# ControlBoard.net
KiCad netlist of a schematic drawn in EAGLE
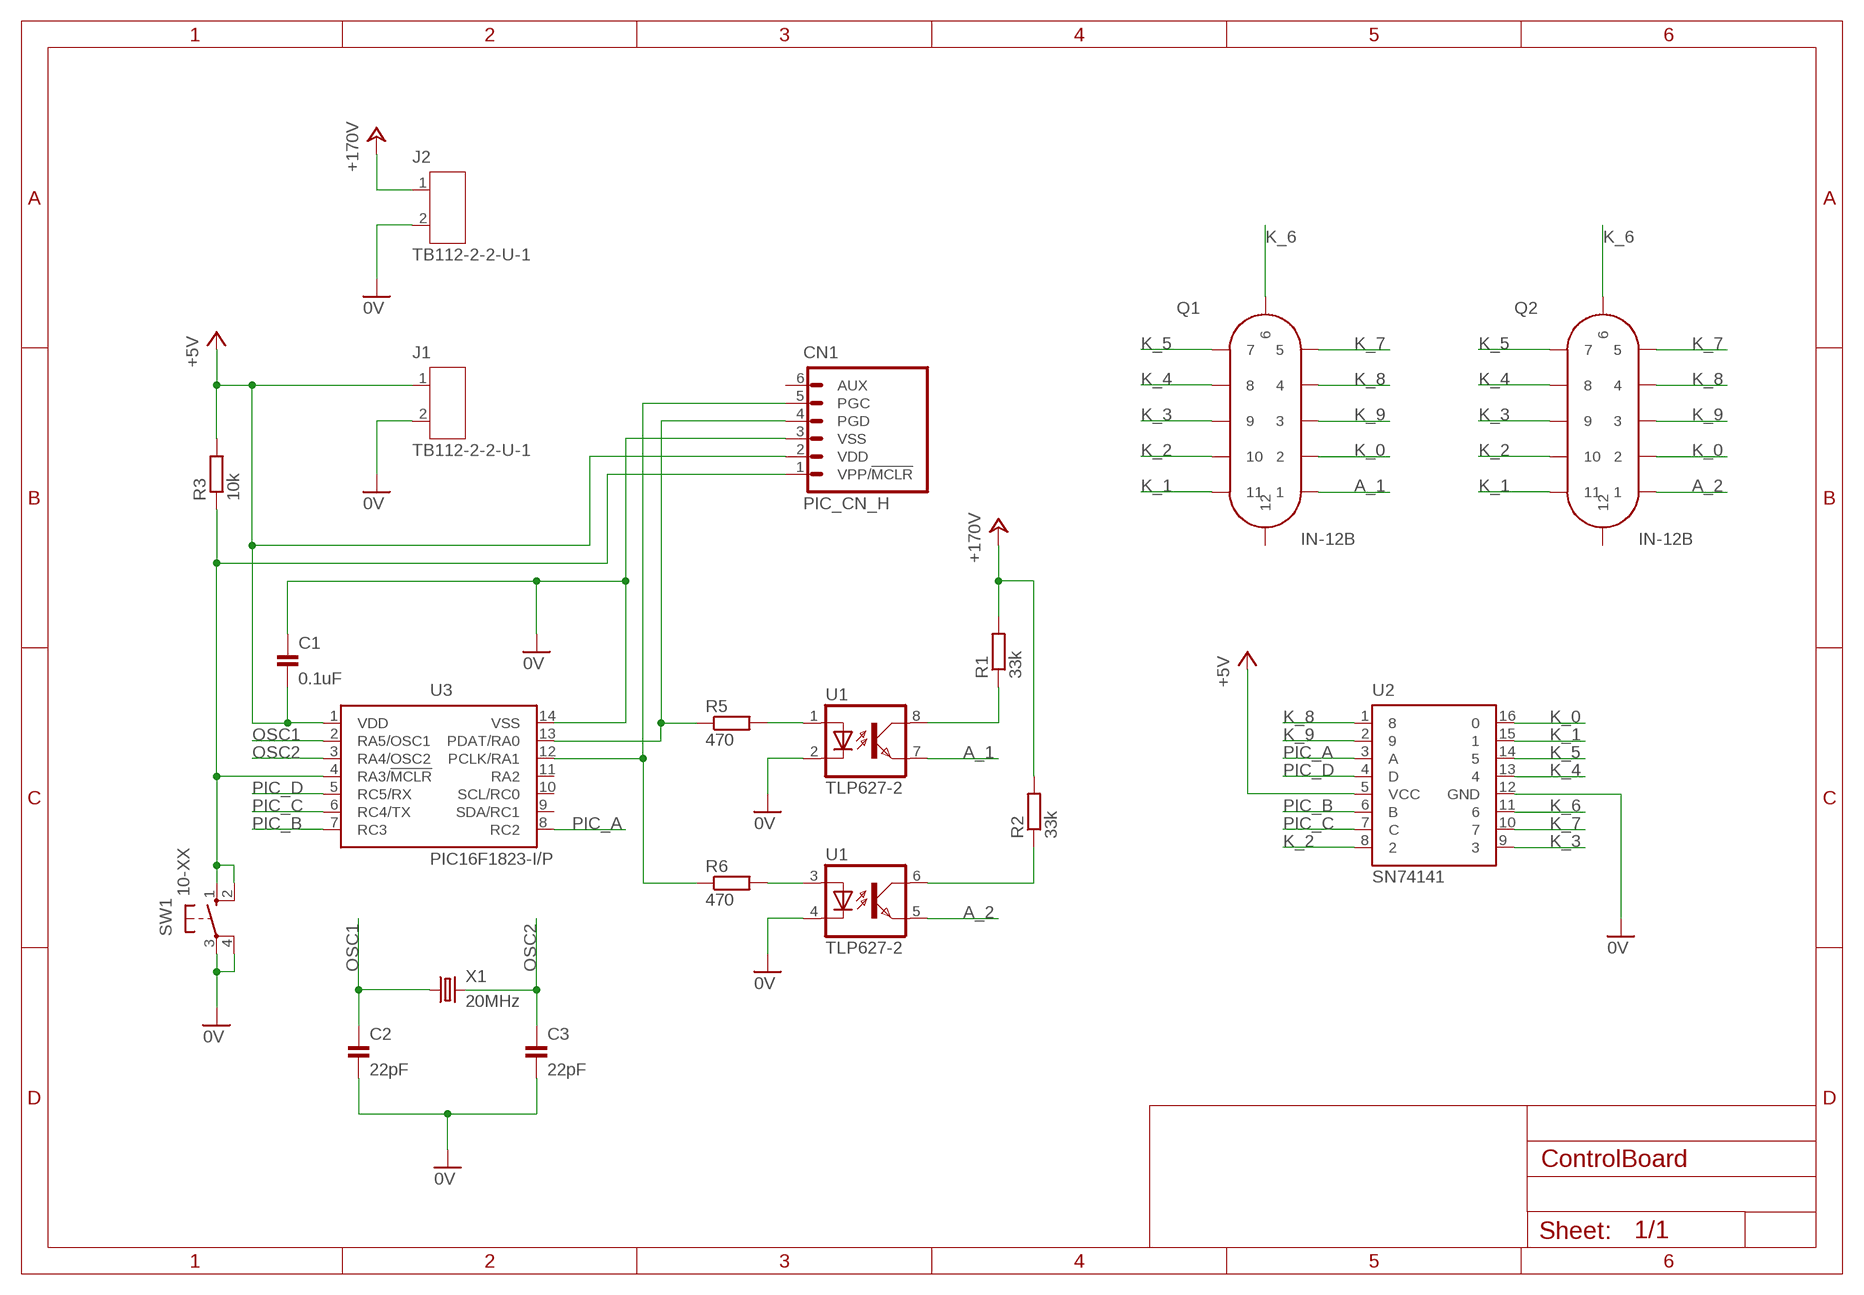
[diagram p0: schematic, sheet 1]

(export (version "E")
  (design (tool "Eeschema 10.0.6"))
  (components
    (comp (ref "C1")
      (value "0.1uF")
      (footprint "eagle-import:CAP_200MIL")
      (libsource (lib "eagle-import") (part "CAP_200MIL"))
    )
    (comp (ref "C2")
      (value "22pF")
      (footprint "eagle-import:CAP_100MIL")
      (libsource (lib "eagle-import") (part "CAP_100MIL"))
    )
    (comp (ref "C3")
      (value "22pF")
      (footprint "eagle-import:CAP_100MIL")
      (libsource (lib "eagle-import") (part "CAP_100MIL"))
    )
    (comp (ref "CN1")
      (value "PIC_CN_H")
      (footprint "eagle-import:HEADER_6PIN")
      (libsource (lib "eagle-import") (part "PIC_CN_H"))
    )
    (comp (ref "J1")
      (value "TB112-2-2-U-1")
      (footprint "eagle-import:TERMINAL_BLOCK_2PIN_200MIL")
      (libsource (lib "eagle-import") (part "TB112-2-2-U-1"))
    )
    (comp (ref "J2")
      (value "TB112-2-2-U-1")
      (footprint "eagle-import:TERMINAL_BLOCK_2PIN_200MIL")
      (libsource (lib "eagle-import") (part "TB112-2-2-U-1"))
    )
    (comp (ref "Q1")
      (value "IN-12B")
      (footprint "eagle-import:IN-12")
      (libsource (lib "eagle-import") (part "IN-12B"))
    )
    (comp (ref "Q2")
      (value "IN-12B")
      (footprint "eagle-import:IN-12")
      (libsource (lib "eagle-import") (part "IN-12B"))
    )
    (comp (ref "R1")
      (value "33k")
      (footprint "eagle-import:RESISTOR_0411_600MIL")
      (libsource (lib "eagle-import") (part "RESISTOR_600MIL"))
    )
    (comp (ref "R2")
      (value "33k")
      (footprint "eagle-import:RESISTOR_0411_600MIL")
      (libsource (lib "eagle-import") (part "RESISTOR_600MIL"))
    )
    (comp (ref "R3")
      (value "10k")
      (footprint "eagle-import:RESISTOR_0411_600MIL")
      (libsource (lib "eagle-import") (part "RESISTOR_600MIL"))
    )
    (comp (ref "R5")
      (value "470")
      (footprint "eagle-import:RESISTOR_0411_600MIL")
      (libsource (lib "eagle-import") (part "RESISTOR_600MIL"))
    )
    (comp (ref "R6")
      (value "470")
      (footprint "eagle-import:RESISTOR_0411_600MIL")
      (libsource (lib "eagle-import") (part "RESISTOR_600MIL"))
    )
    (comp (ref "SW1")
      (value "10-XX")
      (footprint "eagle-import:B3F-10XX")
      (libsource (lib "eagle-import") (part "10-XX"))
    )
    (comp (ref "U1")
      (value "TLP627-2")
      (footprint "eagle-import:DIL08")
      (libsource (lib "eagle-import") (part "TLP627-2"))
    )
    (comp (ref "U2")
      (value "SN74141")
      (footprint "eagle-import:DIL16")
      (libsource (lib "eagle-import") (part "SN74141"))
    )
    (comp (ref "U3")
      (value "PIC16F1823-I/P")
      (footprint "eagle-import:DIL14")
      (libsource (lib "eagle-import") (part "PIC16F1823-I/P"))
    )
    (comp (ref "X1")
      (value "20MHz")
      (footprint "eagle-import:HC-49_S")
      (libsource (lib "eagle-import") (part "HUSG-20.000-20"))
    )
  )
  (nets
    (net (code "1") (name "+5V") (class "Default")
      (node (ref "C1") (pin "2") (pinfunction "2_2") (pintype "passive"))
      (node (ref "CN1") (pin "2") (pinfunction "VDD_2") (pintype "passive"))
      (node (ref "J1") (pin "1") (pinfunction "1_1") (pintype "passive"))
      (node (ref "R3") (pin "2") (pinfunction "2_2") (pintype "passive"))
      (node (ref "U2") (pin "5") (pinfunction "VCC_5") (pintype "passive"))
      (node (ref "U3") (pin "1") (pinfunction "VDD_1") (pintype "passive"))
    )
    (net (code "2") (name "+170V") (class "Default")
      (node (ref "J2") (pin "1") (pinfunction "1_1") (pintype "passive"))
      (node (ref "R1") (pin "2") (pinfunction "2_2") (pintype "passive"))
      (node (ref "R2") (pin "2") (pinfunction "2_2") (pintype "passive"))
    )
    (net (code "3") (name "/A_1") (class "Default")
      (node (ref "Q1") (pin "7") (pinfunction "1_7") (pintype "passive"))
      (node (ref "U1") (pin "7") (pinfunction "EMIT_7") (pintype "passive"))
    )
    (net (code "4") (name "/A_2") (class "Default")
      (node (ref "Q2") (pin "7") (pinfunction "1_7") (pintype "passive"))
      (node (ref "U1") (pin "5") (pinfunction "EMIT_5") (pintype "passive"))
    )
    (net (code "5") (name "/K_0") (class "Default")
      (node (ref "Q1") (pin "8") (pinfunction "2_8") (pintype "passive"))
      (node (ref "Q2") (pin "8") (pinfunction "2_8") (pintype "passive"))
      (node (ref "U2") (pin "16") (pinfunction "0_16") (pintype "passive"))
    )
    (net (code "6") (name "/K_1") (class "Default")
      (node (ref "Q1") (pin "5") (pinfunction "11_5") (pintype "passive"))
      (node (ref "Q2") (pin "5") (pinfunction "11_5") (pintype "passive"))
      (node (ref "U2") (pin "15") (pinfunction "1_15") (pintype "passive"))
    )
    (net (code "7") (name "/K_2") (class "Default")
      (node (ref "Q1") (pin "4") (pinfunction "10_4") (pintype "passive"))
      (node (ref "Q2") (pin "4") (pinfunction "10_4") (pintype "passive"))
      (node (ref "U2") (pin "8") (pinfunction "2_8") (pintype "passive"))
    )
    (net (code "8") (name "/K_3") (class "Default")
      (node (ref "Q1") (pin "3") (pinfunction "9_3") (pintype "passive"))
      (node (ref "Q2") (pin "3") (pinfunction "9_3") (pintype "passive"))
      (node (ref "U2") (pin "9") (pinfunction "3_9") (pintype "passive"))
    )
    (net (code "9") (name "/K_4") (class "Default")
      (node (ref "Q1") (pin "2") (pinfunction "8_2") (pintype "passive"))
      (node (ref "Q2") (pin "2") (pinfunction "8_2") (pintype "passive"))
      (node (ref "U2") (pin "13") (pinfunction "4_13") (pintype "passive"))
    )
    (net (code "10") (name "/K_5") (class "Default")
      (node (ref "Q1") (pin "1") (pinfunction "7_1") (pintype "passive"))
      (node (ref "Q2") (pin "1") (pinfunction "7_1") (pintype "passive"))
      (node (ref "U2") (pin "14") (pinfunction "5_14") (pintype "passive"))
    )
    (net (code "11") (name "/K_6") (class "Default")
      (node (ref "Q1") (pin "12") (pinfunction "6_12") (pintype "passive"))
      (node (ref "Q2") (pin "12") (pinfunction "6_12") (pintype "passive"))
      (node (ref "U2") (pin "11") (pinfunction "6_11") (pintype "passive"))
    )
    (net (code "12") (name "/K_7") (class "Default")
      (node (ref "Q1") (pin "11") (pinfunction "5_11") (pintype "passive"))
      (node (ref "Q2") (pin "11") (pinfunction "5_11") (pintype "passive"))
      (node (ref "U2") (pin "10") (pinfunction "7_10") (pintype "passive"))
    )
    (net (code "13") (name "/K_8") (class "Default")
      (node (ref "Q1") (pin "10") (pinfunction "4_10") (pintype "passive"))
      (node (ref "Q2") (pin "10") (pinfunction "4_10") (pintype "passive"))
      (node (ref "U2") (pin "1") (pinfunction "8_1") (pintype "passive"))
    )
    (net (code "14") (name "/K_9") (class "Default")
      (node (ref "Q1") (pin "9") (pinfunction "3_9") (pintype "passive"))
      (node (ref "Q2") (pin "9") (pinfunction "3_9") (pintype "passive"))
      (node (ref "U2") (pin "2") (pinfunction "9_2") (pintype "passive"))
    )
    (net (code "15") (name "/OSC1") (class "Default")
      (node (ref "C2") (pin "1") (pinfunction "1_1") (pintype "passive"))
      (node (ref "U3") (pin "2") (pinfunction "RA5/OSC1_2") (pintype "bidirectional"))
      (node (ref "X1") (pin "1") (pinfunction "1_1") (pintype "passive"))
    )
    (net (code "16") (name "/OSC2") (class "Default")
      (node (ref "C3") (pin "1") (pinfunction "1_1") (pintype "passive"))
      (node (ref "U3") (pin "3") (pinfunction "RA4/OSC2_3") (pintype "bidirectional"))
      (node (ref "X1") (pin "2") (pinfunction "2_2") (pintype "passive"))
    )
    (net (code "17") (name "/PIC_A") (class "Default")
      (node (ref "U2") (pin "3") (pinfunction "A_3") (pintype "input"))
      (node (ref "U3") (pin "8") (pinfunction "RC2_8") (pintype "bidirectional"))
    )
    (net (code "18") (name "/PIC_B") (class "Default")
      (node (ref "U2") (pin "6") (pinfunction "B_6") (pintype "input"))
      (node (ref "U3") (pin "7") (pinfunction "RC3_7") (pintype "bidirectional"))
    )
    (net (code "19") (name "/PIC_C") (class "Default")
      (node (ref "U2") (pin "7") (pinfunction "C_7") (pintype "input"))
      (node (ref "U3") (pin "6") (pinfunction "RC4/TX_6") (pintype "bidirectional"))
    )
    (net (code "20") (name "/PIC_D") (class "Default")
      (node (ref "U2") (pin "4") (pinfunction "D_4") (pintype "input"))
      (node (ref "U3") (pin "5") (pinfunction "RC5/RX_5") (pintype "bidirectional"))
    )
    (net (code "21") (name "0V") (class "Default")
      (node (ref "C1") (pin "1") (pinfunction "1_1") (pintype "passive"))
      (node (ref "C2") (pin "2") (pinfunction "2_2") (pintype "passive"))
      (node (ref "C3") (pin "2") (pinfunction "2_2") (pintype "passive"))
      (node (ref "CN1") (pin "3") (pinfunction "VSS_3") (pintype "passive"))
      (node (ref "J1") (pin "2") (pinfunction "2_2") (pintype "passive"))
      (node (ref "J2") (pin "2") (pinfunction "2_2") (pintype "passive"))
      (node (ref "SW1") (pin "3") (pinfunction "P_3") (pintype "passive"))
      (node (ref "SW1") (pin "4") (pinfunction "P1_4") (pintype "passive"))
      (node (ref "U1") (pin "2") (pinfunction "C_2") (pintype "passive"))
      (node (ref "U1") (pin "4") (pinfunction "C_4") (pintype "passive"))
      (node (ref "U2") (pin "12") (pinfunction "GND_12") (pintype "passive"))
      (node (ref "U3") (pin "14") (pinfunction "VSS_14") (pintype "passive"))
    )
    (net (code "22") (name "Net-(CN1-PGC)") (class "Default")
      (node (ref "CN1") (pin "5") (pinfunction "PGC_5") (pintype "input"))
      (node (ref "R6") (pin "1") (pinfunction "1_1") (pintype "passive"))
      (node (ref "U3") (pin "12") (pinfunction "PCLK/RA1_12") (pintype "bidirectional"))
    )
    (net (code "23") (name "Net-(CN1-PGD)") (class "Default")
      (node (ref "CN1") (pin "4") (pinfunction "PGD_4") (pintype "bidirectional"))
      (node (ref "R5") (pin "1") (pinfunction "1_1") (pintype "passive"))
      (node (ref "U3") (pin "13") (pinfunction "PDAT/RA0_13") (pintype "bidirectional"))
    )
    (net (code "24") (name "Net-(CN1-VPP{slash}~{MCLR})") (class "Default")
      (node (ref "CN1") (pin "1") (pinfunction "VPP/~{MCLR}_1") (pintype "input"))
      (node (ref "R3") (pin "1") (pinfunction "1_1") (pintype "passive"))
      (node (ref "SW1") (pin "1") (pinfunction "S_1") (pintype "passive"))
      (node (ref "SW1") (pin "2") (pinfunction "S1_2") (pintype "passive"))
      (node (ref "U3") (pin "4") (pinfunction "RA3/~{MCLR}_4") (pintype "bidirectional"))
    )
    (net (code "25") (name "Net-(U1A-A)") (class "Default")
      (node (ref "R5") (pin "2") (pinfunction "2_2") (pintype "passive"))
      (node (ref "U1") (pin "1") (pinfunction "A_1") (pintype "passive"))
    )
    (net (code "26") (name "Net-(U1A-COL)") (class "Default")
      (node (ref "R1") (pin "1") (pinfunction "1_1") (pintype "passive"))
      (node (ref "U1") (pin "8") (pinfunction "COL_8") (pintype "passive"))
    )
    (net (code "27") (name "Net-(U1B-A)") (class "Default")
      (node (ref "R6") (pin "2") (pinfunction "2_2") (pintype "passive"))
      (node (ref "U1") (pin "3") (pinfunction "A_3") (pintype "passive"))
    )
    (net (code "28") (name "Net-(U1B-COL)") (class "Default")
      (node (ref "R2") (pin "1") (pinfunction "1_1") (pintype "passive"))
      (node (ref "U1") (pin "6") (pinfunction "COL_6") (pintype "passive"))
    )
    (net (code "29") (name "unconnected-(CN1-AUX-Pad6)") (class "Default")
      (node (ref "CN1") (pin "6") (pinfunction "AUX_6") (pintype "bidirectional"))
    )
    (net (code "30") (name "unconnected-(Q1-12-Pad6)") (class "Default")
      (node (ref "Q1") (pin "6") (pinfunction "12_6") (pintype "passive"))
    )
    (net (code "31") (name "unconnected-(Q2-12-Pad6)") (class "Default")
      (node (ref "Q2") (pin "6") (pinfunction "12_6") (pintype "passive"))
    )
    (net (code "32") (name "unconnected-(U3-RA2-Pad11)") (class "Default")
      (node (ref "U3") (pin "11") (pinfunction "RA2_11") (pintype "bidirectional"))
    )
    (net (code "33") (name "unconnected-(U3-SCL{slash}RC0-Pad10)") (class "Default")
      (node (ref "U3") (pin "10") (pinfunction "SCL/RC0_10") (pintype "bidirectional"))
    )
    (net (code "34") (name "unconnected-(U3-SDA{slash}RC1-Pad9)") (class "Default")
      (node (ref "U3") (pin "9") (pinfunction "SDA/RC1_9") (pintype "bidirectional"))
    )
  )
)
